# Sheet1.net
KiCad netlist of a schematic drawn in Altium Designer
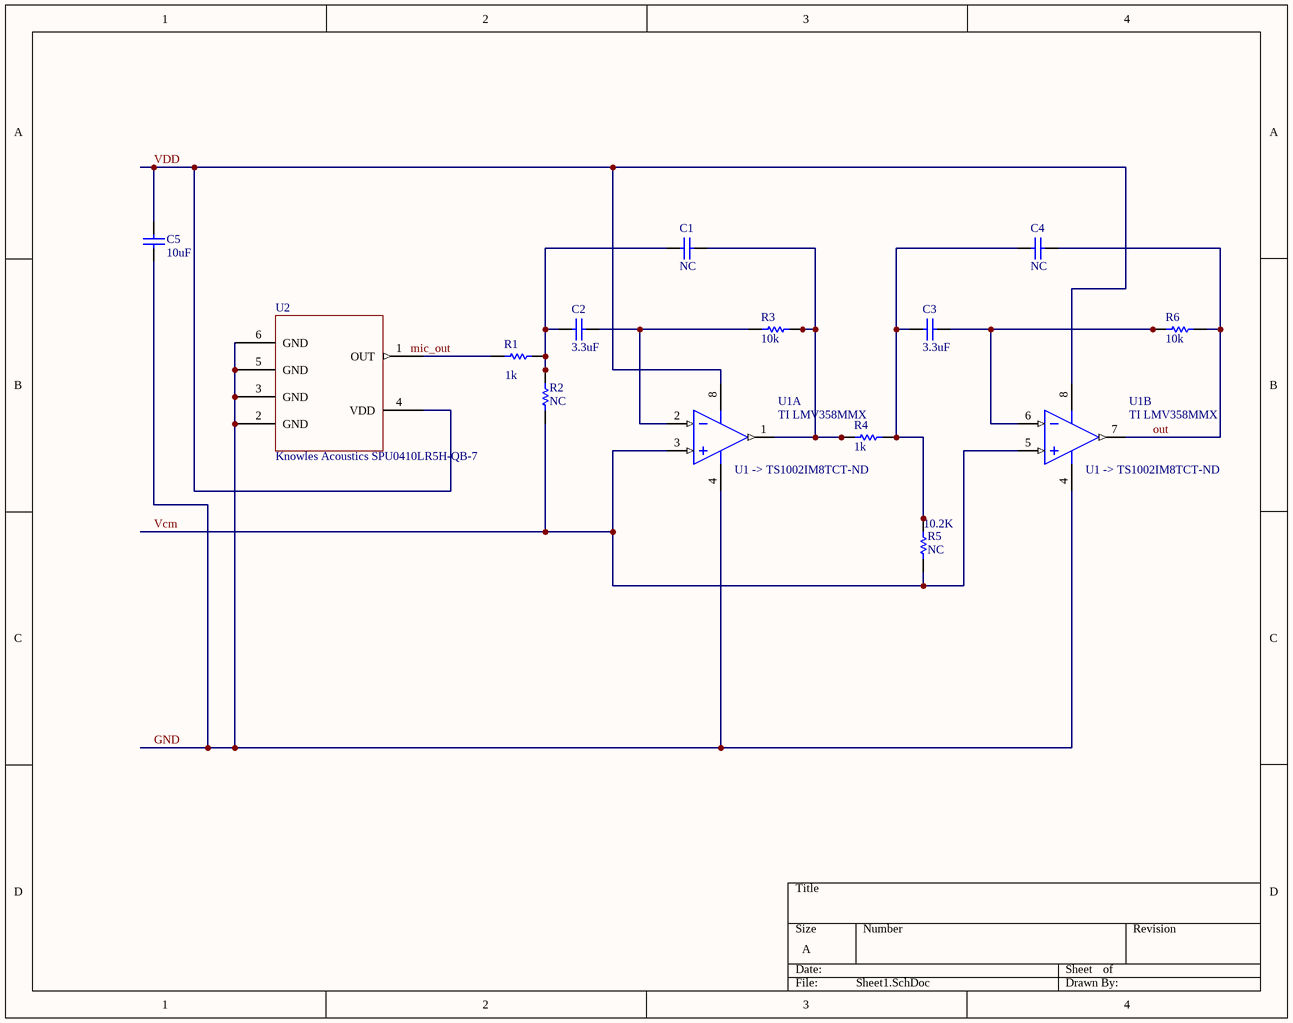
[diagram p0: Sheet1.SchDoc]

(export (version "E")
  (design (tool "Eeschema 10.0.6"))
  (components
    (comp (ref "C1")
      (value "NC")
      (footprint "CAPC1608X08M")
      (description "Generic 0603 Capacitor")
      (libsource (lib "CommunityVault") (part "CMP-nocyn7nhex2srcneo663-2"))
    )
    (comp (ref "C2")
      (value "3.3uF")
      (footprint "CAPC1608X08M")
      (description "Generic 0603 Capacitor")
      (libsource (lib "CommunityVault") (part "CMP-nocyn7nhex2srcneo663-2"))
    )
    (comp (ref "C3")
      (value "3.3uF")
      (footprint "CAPC1608X08M")
      (description "Generic 0603 Capacitor")
      (libsource (lib "CommunityVault") (part "CMP-nocyn7nhex2srcneo663-2"))
    )
    (comp (ref "C4")
      (value "NC")
      (footprint "CAPC1608X08M")
      (description "Generic 0603 Capacitor")
      (libsource (lib "CommunityVault") (part "CMP-nocyn7nhex2srcneo663-2"))
    )
    (comp (ref "C5")
      (value "10uF")
      (footprint "CAPC2013X94X50LL20T25")
      (description "CAP CER 1500PF 50V 10% X7R 0805")
      (libsource (lib "CommunityVault") (part "CMP-126016-2"))
    )
    (comp (ref "R1")
      (value "1k")
      (footprint "RESC1608X06L")
      (description "Generic 0603 Resistor")
      (fields (field (name "TOLERANCE") "1%"))
      (libsource (lib "CommunityVault") (part "CMP-iebvg68tg8mmdpxr2n2a-5"))
    )
    (comp (ref "R2")
      (value "NC")
      (footprint "RESC1608X06L")
      (description "Generic 0603 Resistor")
      (fields (field (name "TOLERANCE") "1%"))
      (libsource (lib "CommunityVault") (part "CMP-iebvg68tg8mmdpxr2n2a-5"))
    )
    (comp (ref "R3")
      (value "10k")
      (footprint "RESC1608X06L")
      (description "Generic 0603 Resistor")
      (fields (field (name "TOLERANCE") "1%"))
      (libsource (lib "CommunityVault") (part "CMP-iebvg68tg8mmdpxr2n2a-5"))
    )
    (comp (ref "R4")
      (value "1k")
      (footprint "RESC1608X06L")
      (description "Generic 0603 Resistor")
      (fields (field (name "TOLERANCE") "1%"))
      (libsource (lib "CommunityVault") (part "CMP-iebvg68tg8mmdpxr2n2a-5"))
    )
    (comp (ref "R5")
      (value "NC")
      (footprint "RESC1608X06L")
      (description "Generic 0603 Resistor")
      (fields (field (name "TOLERANCE") "1%") (field (name "RESISTANCE") "10.2K"))
      (libsource (lib "CommunityVault") (part "CMP-iebvg68tg8mmdpxr2n2a-5"))
    )
    (comp (ref "R6")
      (value "10k")
      (footprint "RESC1608X06L")
      (description "Generic 0603 Resistor")
      (fields (field (name "TOLERANCE") "1%"))
      (libsource (lib "CommunityVault") (part "CMP-iebvg68tg8mmdpxr2n2a-5"))
    )
    (comp (ref "U1")
      (value "TI LMV358MMX")
      (footprint "MSOP08")
      (description "IC OPAMP GP 1MHZ RRO 8VSSOP")
      (libsource (lib "CommunityVault") (part "TI-LMV358-8"))
    )
    (comp (ref "U2")
      (value "Knowles Acoustics SPU0410LR5H-QB-7")
      (footprint "PCB-fhaaljglxn5h86y57i6s-1")
      (description "Mic Mems Analog Omni -38db")
      (fields (field (name "MANUFACTURER PART NUMBER") "SPU0410LR5H-QB-7"))
      (libsource (lib "CommunityVault") (part "SYM-9a235714badd45e4-1"))
    )
  )
  (nets
    (net (code "1") (name "/GND") (class "Default")
      (node (ref "C5") (pin "1") (pinfunction "1_1") (pintype "passive"))
      (node (ref "U1") (pin "4") (pinfunction "GND_4") (pintype "power_in"))
      (node (ref "U2") (pin "2") (pinfunction "GND_2") (pintype "power_in"))
      (node (ref "U2") (pin "3") (pinfunction "GND_3") (pintype "power_in"))
      (node (ref "U2") (pin "5") (pinfunction "GND_5") (pintype "power_in"))
      (node (ref "U2") (pin "6") (pinfunction "GND_6") (pintype "power_in"))
    )
    (net (code "2") (name "/VDD") (class "Default")
      (node (ref "C5") (pin "2") (pinfunction "2_2") (pintype "passive"))
      (node (ref "U1") (pin "8") (pinfunction "VCC+_8") (pintype "power_in"))
      (node (ref "U2") (pin "4") (pinfunction "VDD_4") (pintype "power_in"))
    )
    (net (code "3") (name "/Vcm") (class "Default")
      (node (ref "R2") (pin "1") (pinfunction "1_1") (pintype "passive"))
      (node (ref "R5") (pin "1") (pinfunction "1_1") (pintype "passive"))
      (node (ref "U1") (pin "3") (pinfunction "IN1+_3") (pintype "input"))
      (node (ref "U1") (pin "5") (pinfunction "IN2+_5") (pintype "input"))
    )
    (net (code "5") (name "/out") (class "Default")
      (node (ref "C4") (pin "2") (pinfunction "2_2") (pintype "passive"))
      (node (ref "R6") (pin "2") (pinfunction "2_2") (pintype "passive"))
      (node (ref "U1") (pin "7") (pinfunction "OUT2_7") (pintype "output"))
    )
    (net (code "6") (name "Net-(C1-Pad1)") (class "Default")
      (node (ref "C1") (pin "1") (pinfunction "1_1") (pintype "passive"))
      (node (ref "C2") (pin "1") (pinfunction "1_1") (pintype "passive"))
      (node (ref "R1") (pin "2") (pinfunction "2_2") (pintype "passive"))
      (node (ref "R2") (pin "2") (pinfunction "2_2") (pintype "passive"))
    )
    (net (code "7") (name "Net-(C3-Pad1)") (class "Default")
      (node (ref "C3") (pin "1") (pinfunction "1_1") (pintype "passive"))
      (node (ref "C4") (pin "1") (pinfunction "1_1") (pintype "passive"))
      (node (ref "R4") (pin "2") (pinfunction "2_2") (pintype "passive"))
      (node (ref "R5") (pin "2") (pinfunction "2_2") (pintype "passive"))
    )
    (net (code "8") (name "Net-(U1A-IN1-)") (class "Default")
      (node (ref "C2") (pin "2") (pinfunction "2_2") (pintype "passive"))
      (node (ref "R3") (pin "1") (pinfunction "1_1") (pintype "passive"))
      (node (ref "U1") (pin "2") (pinfunction "IN1-_2") (pintype "input"))
    )
    (net (code "9") (name "Net-(U1A-OUT1)") (class "Default")
      (node (ref "C1") (pin "2") (pinfunction "2_2") (pintype "passive"))
      (node (ref "R3") (pin "2") (pinfunction "2_2") (pintype "passive"))
      (node (ref "R4") (pin "1") (pinfunction "1_1") (pintype "passive"))
      (node (ref "U1") (pin "1") (pinfunction "OUT1_1") (pintype "output"))
    )
    (net (code "10") (name "Net-(U1B-IN2-)") (class "Default")
      (node (ref "C3") (pin "2") (pinfunction "2_2") (pintype "passive"))
      (node (ref "R6") (pin "1") (pinfunction "1_1") (pintype "passive"))
      (node (ref "U1") (pin "6") (pinfunction "IN2-_6") (pintype "input"))
    )
    (net (code "11") (name "Net-(U2-OUT)") (class "Default")
      (node (ref "R1") (pin "1") (pinfunction "1_1") (pintype "passive"))
      (node (ref "U2") (pin "1") (pinfunction "OUT_1") (pintype "output"))
    )
  )
)
